# Lcd.net
KiCad netlist of a schematic drawn in EAGLE
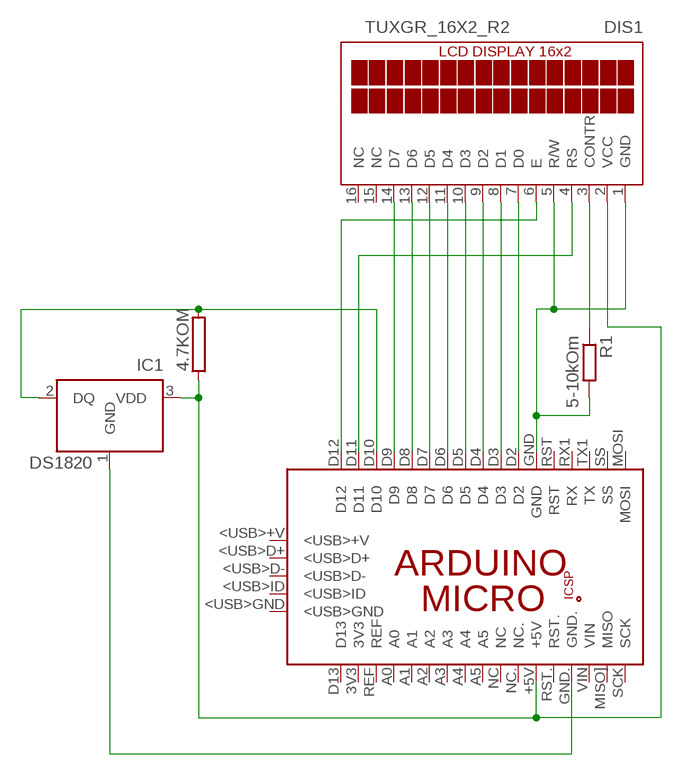
[diagram p0: schematic, sheet 1]

(export (version "E")
  (design (tool "Eeschema 10.0.6"))
  (components
    (comp (ref "4.7KOM")
      (value "RCA4055")
      (footprint "eagle-import:CA4055")
      (libsource (lib "eagle-import") (part "RCA4055"))
    )
    (comp (ref "DIS1")
      (value "TUXGR_16X2_R2")
      (footprint "eagle-import:TUXGR_16X2_R2")
      (libsource (lib "eagle-import") (part "TUXGR_16X2_R2"))
    )
    (comp (ref "IC1")
      (value "DS1820")
      (footprint "eagle-import:TO-92")
      (libsource (lib "eagle-import") (part "DS1820"))
    )
    (comp (ref "PCB1")
      (value "ARDUINO_MICRO")
      (footprint "eagle-import:ARDUINO_MICRO")
      (libsource (lib "eagle-import") (part "ARDUINO_MICRO"))
    )
    (comp (ref "R1")
      (value "5-10kOm")
      (footprint "eagle-import:0204_7")
      (libsource (lib "eagle-import") (part "R-EU_0204/7"))
    )
  )
  (nets
    (net (code "1") (name "Net-(DIS1-CONTR)") (class "Default")
      (node (ref "DIS1") (pin "3") (pinfunction "CONTR_3") (pintype "input"))
      (node (ref "R1") (pin "1") (pinfunction "1_1") (pintype "passive"))
    )
    (net (code "2") (name "Net-(DIS1-D0)") (class "Default")
      (node (ref "DIS1") (pin "7") (pinfunction "D0_7") (pintype "input"))
      (node (ref "PCB1") (pin "D2") (pinfunction "D2_D2") (pintype "bidirectional"))
    )
    (net (code "3") (name "Net-(DIS1-D1)") (class "Default")
      (node (ref "DIS1") (pin "8") (pinfunction "D1_8") (pintype "input"))
      (node (ref "PCB1") (pin "D3") (pinfunction "D3_D3") (pintype "bidirectional"))
    )
    (net (code "4") (name "Net-(DIS1-D2)") (class "Default")
      (node (ref "DIS1") (pin "9") (pinfunction "D2_9") (pintype "input"))
      (node (ref "PCB1") (pin "D4") (pinfunction "D4_D4") (pintype "bidirectional"))
    )
    (net (code "5") (name "Net-(DIS1-D3)") (class "Default")
      (node (ref "DIS1") (pin "10") (pinfunction "D3_10") (pintype "input"))
      (node (ref "PCB1") (pin "D5") (pinfunction "D5_D5") (pintype "bidirectional"))
    )
    (net (code "6") (name "Net-(DIS1-D4)") (class "Default")
      (node (ref "DIS1") (pin "11") (pinfunction "D4_11") (pintype "input"))
      (node (ref "PCB1") (pin "D6") (pinfunction "D6_D6") (pintype "bidirectional"))
    )
    (net (code "7") (name "Net-(DIS1-D5)") (class "Default")
      (node (ref "DIS1") (pin "12") (pinfunction "D5_12") (pintype "input"))
      (node (ref "PCB1") (pin "D7") (pinfunction "D7_D7") (pintype "bidirectional"))
    )
    (net (code "8") (name "Net-(DIS1-D6)") (class "Default")
      (node (ref "DIS1") (pin "13") (pinfunction "D6_13") (pintype "input"))
      (node (ref "PCB1") (pin "D8") (pinfunction "D8_D8") (pintype "bidirectional"))
    )
    (net (code "9") (name "Net-(DIS1-D7)") (class "Default")
      (node (ref "DIS1") (pin "14") (pinfunction "D7_14") (pintype "input"))
      (node (ref "PCB1") (pin "D9") (pinfunction "D9_D9") (pintype "bidirectional"))
    )
    (net (code "10") (name "Net-(DIS1-E)") (class "Default")
      (node (ref "DIS1") (pin "6") (pinfunction "E_6") (pintype "input"))
      (node (ref "PCB1") (pin "D12") (pinfunction "D12_D12") (pintype "bidirectional"))
    )
    (net (code "11") (name "Net-(DIS1-GND)") (class "Default")
      (node (ref "DIS1") (pin "1") (pinfunction "GND_1") (pintype "power_in"))
      (node (ref "DIS1") (pin "5") (pinfunction "R/W_5") (pintype "input"))
      (node (ref "PCB1") (pin "GND") (pinfunction "GND_GND") (pintype "bidirectional"))
      (node (ref "R1") (pin "2") (pinfunction "2_2") (pintype "passive"))
    )
    (net (code "12") (name "Net-(DIS1-RS)") (class "Default")
      (node (ref "DIS1") (pin "4") (pinfunction "RS_4") (pintype "input"))
      (node (ref "PCB1") (pin "D11") (pinfunction "D11_D11") (pintype "bidirectional"))
    )
    (net (code "13") (name "Net-(DIS1-VCC)") (class "Default")
      (node (ref "4.7KOM") (pin "1") (pinfunction "1_1") (pintype "passive"))
      (node (ref "DIS1") (pin "2") (pinfunction "VCC_2") (pintype "power_in"))
      (node (ref "IC1") (pin "3") (pinfunction "VDD_3") (pintype "input"))
      (node (ref "PCB1") (pin "+5V") (pinfunction "+5V_+5V") (pintype "bidirectional"))
    )
    (net (code "14") (name "Net-(IC1-DQ)") (class "Default")
      (node (ref "4.7KOM") (pin "2") (pinfunction "2_2") (pintype "passive"))
      (node (ref "IC1") (pin "2") (pinfunction "DQ_2") (pintype "output"))
      (node (ref "PCB1") (pin "D10") (pinfunction "D10_D10") (pintype "bidirectional"))
    )
    (net (code "15") (name "Net-(IC1-GND)") (class "Default")
      (node (ref "IC1") (pin "1") (pinfunction "GND_1") (pintype "power_in"))
      (node (ref "PCB1") (pin "GND.") (pinfunction "GND._GND.") (pintype "bidirectional"))
    )
    (net (code "16") (name "unconnected-(DIS1-NC-Pad15)") (class "Default")
      (node (ref "DIS1") (pin "15") (pinfunction "NC_15") (pintype "no_connect"))
    )
    (net (code "17") (name "unconnected-(DIS1-NC-Pad16)") (class "Default")
      (node (ref "DIS1") (pin "16") (pinfunction "NC_16") (pintype "no_connect"))
    )
    (net (code "18") (name "unconnected-(PCB1-MISO-PadMISO])") (class "Default")
      (node (ref "PCB1") (pin "MISO]") (pinfunction "MISO_MISO]") (pintype "bidirectional"))
    )
    (net (code "19") (name "unconnected-(PCB1-Pad3V3)") (class "Default")
      (node (ref "PCB1") (pin "3V3") (pinfunction "3V3_3V3") (pintype "bidirectional"))
    )
    (net (code "20") (name "unconnected-(PCB1-Pad5V)") (class "Default")
      (node (ref "PCB1") (pin "5V") (pinfunction "5V_5V") (pintype "bidirectional"))
    )
    (net (code "21") (name "unconnected-(PCB1-Pad<USB>+V)") (class "Default")
      (node (ref "PCB1") (pin "<USB>+V") (pinfunction "<USB>+V_<USB>+V") (pintype "bidirectional"))
    )
    (net (code "22") (name "unconnected-(PCB1-Pad<USB>D+)") (class "Default")
      (node (ref "PCB1") (pin "<USB>D+") (pinfunction "<USB>D+_<USB>D+") (pintype "bidirectional"))
    )
    (net (code "23") (name "unconnected-(PCB1-Pad<USB>D-)") (class "Default")
      (node (ref "PCB1") (pin "<USB>D-") (pinfunction "<USB>D-_<USB>D-") (pintype "bidirectional"))
    )
    (net (code "24") (name "unconnected-(PCB1-Pad<USB>GND)") (class "Default")
      (node (ref "PCB1") (pin "<USB>GND") (pinfunction "<USB>GND_<USB>GND") (pintype "bidirectional"))
    )
    (net (code "25") (name "unconnected-(PCB1-Pad<USB>ID)") (class "Default")
      (node (ref "PCB1") (pin "<USB>ID") (pinfunction "<USB>ID_<USB>ID") (pintype "bidirectional"))
    )
    (net (code "26") (name "unconnected-(PCB1-PadA0)") (class "Default")
      (node (ref "PCB1") (pin "A0") (pinfunction "A0_A0") (pintype "bidirectional"))
    )
    (net (code "27") (name "unconnected-(PCB1-PadA1)") (class "Default")
      (node (ref "PCB1") (pin "A1") (pinfunction "A1_A1") (pintype "bidirectional"))
    )
    (net (code "28") (name "unconnected-(PCB1-PadA2)") (class "Default")
      (node (ref "PCB1") (pin "A2") (pinfunction "A2_A2") (pintype "bidirectional"))
    )
    (net (code "29") (name "unconnected-(PCB1-PadA3)") (class "Default")
      (node (ref "PCB1") (pin "A3") (pinfunction "A3_A3") (pintype "bidirectional"))
    )
    (net (code "30") (name "unconnected-(PCB1-PadA4)") (class "Default")
      (node (ref "PCB1") (pin "A4") (pinfunction "A4_A4") (pintype "bidirectional"))
    )
    (net (code "31") (name "unconnected-(PCB1-PadA5)") (class "Default")
      (node (ref "PCB1") (pin "A5") (pinfunction "A5_A5") (pintype "bidirectional"))
    )
    (net (code "32") (name "unconnected-(PCB1-PadD13)") (class "Default")
      (node (ref "PCB1") (pin "D13") (pinfunction "D13_D13") (pintype "bidirectional"))
    )
    (net (code "33") (name "unconnected-(PCB1-PadGND_)") (class "Default")
      (node (ref "PCB1") (pin "GND_") (pinfunction "GND__GND_") (pintype "bidirectional"))
    )
    (net (code "34") (name "unconnected-(PCB1-PadMISO.)") (class "Default")
      (node (ref "PCB1") (pin "MISO.") (pinfunction "MISO._MISO.") (pintype "bidirectional"))
    )
    (net (code "35") (name "unconnected-(PCB1-PadMOSI)") (class "Default")
      (node (ref "PCB1") (pin "MOSI") (pinfunction "MOSI_MOSI") (pintype "bidirectional"))
    )
    (net (code "36") (name "unconnected-(PCB1-PadMOSI.)") (class "Default")
      (node (ref "PCB1") (pin "MOSI.") (pinfunction "MOSI._MOSI.") (pintype "bidirectional"))
    )
    (net (code "37") (name "unconnected-(PCB1-PadNC)") (class "Default")
      (node (ref "PCB1") (pin "NC") (pinfunction "NC_NC") (pintype "bidirectional"))
    )
    (net (code "38") (name "unconnected-(PCB1-PadNC.)") (class "Default")
      (node (ref "PCB1") (pin "NC.") (pinfunction "NC._NC.") (pintype "bidirectional"))
    )
    (net (code "39") (name "unconnected-(PCB1-PadREF)") (class "Default")
      (node (ref "PCB1") (pin "REF") (pinfunction "REF_REF") (pintype "bidirectional"))
    )
    (net (code "40") (name "unconnected-(PCB1-PadRESET..)") (class "Default")
      (node (ref "PCB1") (pin "RESET..") (pinfunction "RESET.._RESET..") (pintype "bidirectional"))
    )
    (net (code "41") (name "unconnected-(PCB1-PadRST)") (class "Default")
      (node (ref "PCB1") (pin "RST") (pinfunction "RST_RST") (pintype "bidirectional"))
    )
    (net (code "42") (name "unconnected-(PCB1-PadRST.)") (class "Default")
      (node (ref "PCB1") (pin "RST.") (pinfunction "RST._RST.") (pintype "bidirectional"))
    )
    (net (code "43") (name "unconnected-(PCB1-PadSCK)") (class "Default")
      (node (ref "PCB1") (pin "SCK") (pinfunction "SCK_SCK") (pintype "bidirectional"))
    )
    (net (code "44") (name "unconnected-(PCB1-PadSCK.)") (class "Default")
      (node (ref "PCB1") (pin "SCK.") (pinfunction "SCK._SCK.") (pintype "bidirectional"))
    )
    (net (code "45") (name "unconnected-(PCB1-PadSS)") (class "Default")
      (node (ref "PCB1") (pin "SS") (pinfunction "SS_SS") (pintype "bidirectional"))
    )
    (net (code "46") (name "unconnected-(PCB1-PadVIN)") (class "Default")
      (node (ref "PCB1") (pin "VIN") (pinfunction "VIN_VIN") (pintype "bidirectional"))
    )
    (net (code "47") (name "unconnected-(PCB1-RX-PadRX1)") (class "Default")
      (node (ref "PCB1") (pin "RX1") (pinfunction "RX_RX1") (pintype "bidirectional"))
    )
    (net (code "48") (name "unconnected-(PCB1-TX-PadTX1)") (class "Default")
      (node (ref "PCB1") (pin "TX1") (pinfunction "TX_TX1") (pintype "bidirectional"))
    )
  )
)
